# Schematic.net
KiCad netlist of a schematic drawn in EAGLE
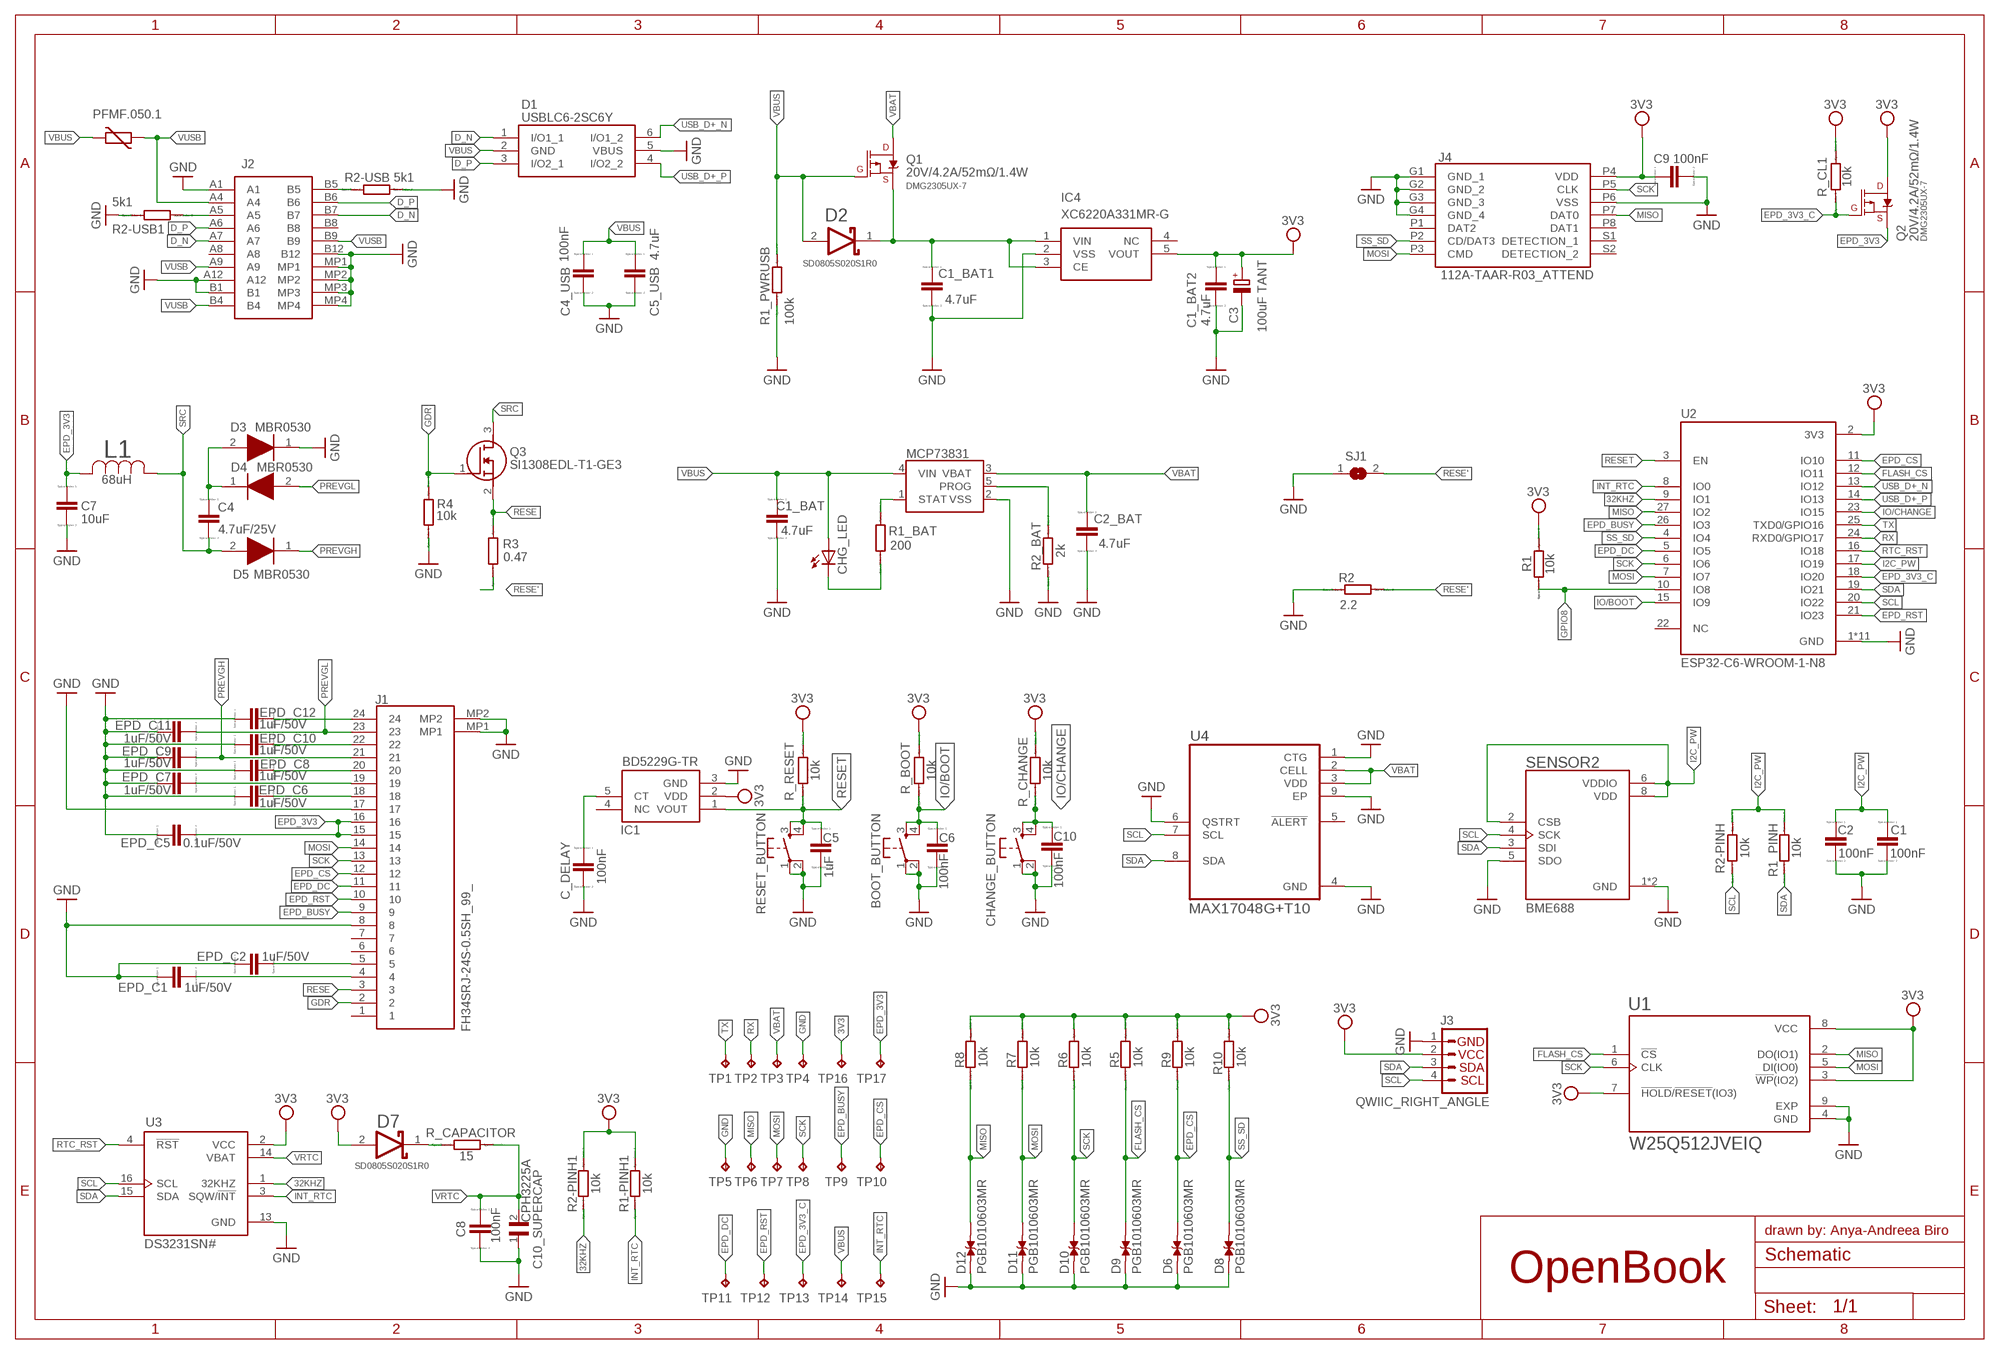
[diagram p0: schematic, sheet 1]

(export (version "E")
  (design (tool "Eeschema 10.0.6"))
  (components
    (comp (ref "BOOT_BUTTON")
      (value "BUTTON_CUSYOMV1")
      (footprint "eagle-import:MYBUTTON")
      (libsource (lib "eagle-import") (part "BUTTON_CUSYOMV1"))
    )
    (comp (ref "C1")
      (value "100nF")
      (footprint "eagle-import:ESP32_WROVER_EAGLE-LTSPICE_C0402")
      (libsource (lib "eagle-import") (part "ESP32_WROVER_EAGLE-LTSPICE_CC0402"))
    )
    (comp (ref "C1_BAT")
      (value "4.7uF")
      (footprint "eagle-import:ESP32_WROVER_EAGLE-LTSPICE_C0402")
      (libsource (lib "eagle-import") (part "ESP32_WROVER_EAGLE-LTSPICE_CC0402"))
    )
    (comp (ref "C1_BAT1")
      (value "4.7uF")
      (footprint "eagle-import:ESP32_WROVER_EAGLE-LTSPICE_C0402")
      (libsource (lib "eagle-import") (part "ESP32_WROVER_EAGLE-LTSPICE_CC0402"))
    )
    (comp (ref "C1_BAT2")
      (value "4.7uF")
      (footprint "eagle-import:ESP32_WROVER_EAGLE-LTSPICE_C0402")
      (libsource (lib "eagle-import") (part "ESP32_WROVER_EAGLE-LTSPICE_CC0402"))
    )
    (comp (ref "C2")
      (value "100nF")
      (footprint "eagle-import:ESP32_WROVER_EAGLE-LTSPICE_C0402")
      (libsource (lib "eagle-import") (part "ESP32_WROVER_EAGLE-LTSPICE_CC0402"))
    )
    (comp (ref "C2_BAT")
      (value "4.7uF")
      (footprint "eagle-import:ESP32_WROVER_EAGLE-LTSPICE_C0402")
      (libsource (lib "eagle-import") (part "ESP32_WROVER_EAGLE-LTSPICE_CC0402"))
    )
    (comp (ref "C3")
      (value "100uF TANT")
      (footprint "eagle-import:RCL_CT3528")
      (libsource (lib "eagle-import") (part "RCL_CPOL-EUCT3528"))
    )
    (comp (ref "C4")
      (value "4.7uF/25V")
      (footprint "eagle-import:ESP32_WROVER_EAGLE-LTSPICE_C0402")
      (libsource (lib "eagle-import") (part "ESP32_WROVER_EAGLE-LTSPICE_CC0402"))
    )
    (comp (ref "C4_USB")
      (value "100nF")
      (footprint "eagle-import:ESP32_WROVER_EAGLE-LTSPICE_C0402")
      (libsource (lib "eagle-import") (part "ESP32_WROVER_EAGLE-LTSPICE_CC0402"))
    )
    (comp (ref "C5")
      (value "1uF")
      (footprint "eagle-import:ESP32_WROVER_EAGLE-LTSPICE_C0402")
      (libsource (lib "eagle-import") (part "ESP32_WROVER_EAGLE-LTSPICE_CC0402"))
    )
    (comp (ref "C5_USB")
      (value "4.7uF")
      (footprint "eagle-import:ESP32_WROVER_EAGLE-LTSPICE_C0402")
      (libsource (lib "eagle-import") (part "ESP32_WROVER_EAGLE-LTSPICE_CC0402"))
    )
    (comp (ref "C6")
      (value "100nF")
      (footprint "eagle-import:ESP32_WROVER_EAGLE-LTSPICE_C0402")
      (libsource (lib "eagle-import") (part "ESP32_WROVER_EAGLE-LTSPICE_CC0402"))
    )
    (comp (ref "C7")
      (value "10uF")
      (footprint "eagle-import:ESP32_WROVER_EAGLE-LTSPICE_C0402")
      (libsource (lib "eagle-import") (part "ESP32_WROVER_EAGLE-LTSPICE_CC0402"))
    )
    (comp (ref "C8")
      (value "100nF")
      (footprint "eagle-import:ESP32_WROVER_EAGLE-LTSPICE_C0402")
      (libsource (lib "eagle-import") (part "ESP32_WROVER_EAGLE-LTSPICE_CC0402"))
    )
    (comp (ref "C9")
      (value "100nF")
      (footprint "eagle-import:ESP32_WROVER_EAGLE-LTSPICE_C0402")
      (libsource (lib "eagle-import") (part "ESP32_WROVER_EAGLE-LTSPICE_CC0402"))
    )
    (comp (ref "C10")
      (value "100nF")
      (footprint "eagle-import:ESP32_WROVER_EAGLE-LTSPICE_C0402")
      (libsource (lib "eagle-import") (part "ESP32_WROVER_EAGLE-LTSPICE_CC0402"))
    )
    (comp (ref "C10_SUPERCAP")
      (value "CPH3225A")
      (footprint "eagle-import:CAPCP3225X100N")
      (fields (field (name "MF") "Seiko Instruments"))
      (libsource (lib "eagle-import") (part "CPH3225A"))
    )
    (comp (ref "CHANGE_BUTTON")
      (value "BUTTON_CUSYOMV1")
      (footprint "eagle-import:MYBUTTON")
      (libsource (lib "eagle-import") (part "BUTTON_CUSYOMV1"))
    )
    (comp (ref "CHG_LED")
      (value "ADAFRUIT_LEDCHIP-LED0603")
      (footprint "eagle-import:ADAFRUIT_CHIP-LED0603")
      (libsource (lib "eagle-import") (part "ADAFRUIT_LEDCHIP-LED0603"))
    )
    (comp (ref "C_DELAY")
      (value "100nF")
      (footprint "eagle-import:ESP32_WROVER_EAGLE-LTSPICE_C0402")
      (libsource (lib "eagle-import") (part "ESP32_WROVER_EAGLE-LTSPICE_CC0402"))
    )
    (comp (ref "D1")
      (value "USBLC6-2SC6Y")
      (footprint "eagle-import:SOT95P280X145-6N")
      (fields (field (name "MF") "STMicroelectronics"))
      (libsource (lib "eagle-import") (part "USBLC6-2SC6Y"))
    )
    (comp (ref "D2")
      (value "ESP32_WROVER_AVX---SD0805S020S1R0_AVX_SD0805S020S1R0_0_0AVX_SD0805S020S1R0_0_0")
      (footprint "eagle-import:ESP32_WROVER_AVX---SD0805S020S1R0_AVX_SD0805S020S1R0_0")
      (fields
        (field (name "DIGIKEY_PART_NUMBER") "478-7800-1-ND")
        (field (name "MF") "AVX")
        (field (name "MOUSER_PART_NUMBER") "581-SD0805S020S1R0")
      )
      (libsource (lib "eagle-import") (part "ESP32_WROVER_AVX---SD0805S020S1R0_AVX_SD0805S020S1R0_0_0AVX_SD0805S020S1R0_0_0"))
    )
    (comp (ref "D3")
      (value "MBR0530")
      (footprint "eagle-import:SOD3716X135N")
      (fields (field (name "MF") "ON Semiconductor"))
      (libsource (lib "eagle-import") (part "MBR0530"))
    )
    (comp (ref "D4")
      (value "MBR0530")
      (footprint "eagle-import:SOD3716X135N")
      (fields (field (name "MF") "ON Semiconductor"))
      (libsource (lib "eagle-import") (part "MBR0530"))
    )
    (comp (ref "D5")
      (value "MBR0530")
      (footprint "eagle-import:SOD3716X135N")
      (fields (field (name "MF") "ON Semiconductor"))
      (libsource (lib "eagle-import") (part "MBR0530"))
    )
    (comp (ref "D6")
      (value "PGB1010603MR")
      (footprint "eagle-import:DIOC1608X36N")
      (fields (field (name "MF") "Littelfuse Inc."))
      (libsource (lib "eagle-import") (part "PGB1010603MR"))
    )
    (comp (ref "D7")
      (value "ESP32_WROVER_AVX---SD0805S020S1R0_AVX_SD0805S020S1R0_0_0AVX_SD0805S020S1R0_0_0")
      (footprint "eagle-import:ESP32_WROVER_AVX---SD0805S020S1R0_AVX_SD0805S020S1R0_0")
      (fields
        (field (name "DIGIKEY_PART_NUMBER") "478-7800-1-ND")
        (field (name "MF") "AVX")
        (field (name "MOUSER_PART_NUMBER") "581-SD0805S020S1R0")
      )
      (libsource (lib "eagle-import") (part "ESP32_WROVER_AVX---SD0805S020S1R0_AVX_SD0805S020S1R0_0_0AVX_SD0805S020S1R0_0_0"))
    )
    (comp (ref "D8")
      (value "PGB1010603MR")
      (footprint "eagle-import:DIOC1608X36N")
      (fields (field (name "MF") "Littelfuse Inc."))
      (libsource (lib "eagle-import") (part "PGB1010603MR"))
    )
    (comp (ref "D9")
      (value "PGB1010603MR")
      (footprint "eagle-import:DIOC1608X36N")
      (fields (field (name "MF") "Littelfuse Inc."))
      (libsource (lib "eagle-import") (part "PGB1010603MR"))
    )
    (comp (ref "D10")
      (value "PGB1010603MR")
      (footprint "eagle-import:DIOC1608X36N")
      (fields (field (name "MF") "Littelfuse Inc."))
      (libsource (lib "eagle-import") (part "PGB1010603MR"))
    )
    (comp (ref "D11")
      (value "PGB1010603MR")
      (footprint "eagle-import:DIOC1608X36N")
      (fields (field (name "MF") "Littelfuse Inc."))
      (libsource (lib "eagle-import") (part "PGB1010603MR"))
    )
    (comp (ref "D12")
      (value "PGB1010603MR")
      (footprint "eagle-import:DIOC1608X36N")
      (fields (field (name "MF") "Littelfuse Inc."))
      (libsource (lib "eagle-import") (part "PGB1010603MR"))
    )
    (comp (ref "EPD_C1")
      (value "1uF/50V")
      (footprint "eagle-import:ESP32_WROVER_EAGLE-LTSPICE_C0402")
      (libsource (lib "eagle-import") (part "ESP32_WROVER_EAGLE-LTSPICE_CC0402"))
    )
    (comp (ref "EPD_C2")
      (value "1uF/50V")
      (footprint "eagle-import:ESP32_WROVER_EAGLE-LTSPICE_C0402")
      (libsource (lib "eagle-import") (part "ESP32_WROVER_EAGLE-LTSPICE_CC0402"))
    )
    (comp (ref "EPD_C5")
      (value "0.1uF/50V")
      (footprint "eagle-import:ESP32_WROVER_EAGLE-LTSPICE_C0402")
      (libsource (lib "eagle-import") (part "ESP32_WROVER_EAGLE-LTSPICE_CC0402"))
    )
    (comp (ref "EPD_C6")
      (value "1uF/50V")
      (footprint "eagle-import:ESP32_WROVER_EAGLE-LTSPICE_C0402")
      (libsource (lib "eagle-import") (part "ESP32_WROVER_EAGLE-LTSPICE_CC0402"))
    )
    (comp (ref "EPD_C7")
      (value "1uF/50V")
      (footprint "eagle-import:ESP32_WROVER_EAGLE-LTSPICE_C0402")
      (libsource (lib "eagle-import") (part "ESP32_WROVER_EAGLE-LTSPICE_CC0402"))
    )
    (comp (ref "EPD_C8")
      (value "1uF/50V")
      (footprint "eagle-import:ESP32_WROVER_EAGLE-LTSPICE_C0402")
      (libsource (lib "eagle-import") (part "ESP32_WROVER_EAGLE-LTSPICE_CC0402"))
    )
    (comp (ref "EPD_C9")
      (value "1uF/50V")
      (footprint "eagle-import:ESP32_WROVER_EAGLE-LTSPICE_C0402")
      (libsource (lib "eagle-import") (part "ESP32_WROVER_EAGLE-LTSPICE_CC0402"))
    )
    (comp (ref "EPD_C10")
      (value "1uF/50V")
      (footprint "eagle-import:ESP32_WROVER_EAGLE-LTSPICE_C0402")
      (libsource (lib "eagle-import") (part "ESP32_WROVER_EAGLE-LTSPICE_CC0402"))
    )
    (comp (ref "EPD_C11")
      (value "1uF/50V")
      (footprint "eagle-import:ESP32_WROVER_EAGLE-LTSPICE_C0402")
      (libsource (lib "eagle-import") (part "ESP32_WROVER_EAGLE-LTSPICE_CC0402"))
    )
    (comp (ref "EPD_C12")
      (value "1uF/50V")
      (footprint "eagle-import:ESP32_WROVER_EAGLE-LTSPICE_C0402")
      (libsource (lib "eagle-import") (part "ESP32_WROVER_EAGLE-LTSPICE_CC0402"))
    )
    (comp (ref "IC1")
      (value "BD5229G-TR")
      (footprint "eagle-import:SOT95P280X125-5N")
      (fields (field (name "MOUSER_PART_NUMBER") "755-BD5229G-TR"))
      (libsource (lib "eagle-import") (part "BD5229G-TR"))
    )
    (comp (ref "IC4")
      (value "XC6220A331MR-G")
      (footprint "eagle-import:SOT95P280X120-5N")
      (fields (field (name "MOUSER_PART_NUMBER") "865-XC6220A331MR-G"))
      (libsource (lib "eagle-import") (part "XC6220A331MR-G"))
    )
    (comp (ref "J1")
      (value "FH34SRJ-24S-0.5SH_99_")
      (footprint "eagle-import:FH34SRJ24S05SH99")
      (fields
        (field (name "MANUFACTURER_PART_NUMBER") "FH34SRJ-24S-0.5SH(99)")
        (field (name "MOUSER_PART_NUMBER") "798-FH34SRJ24S05SH99")
      )
      (libsource (lib "eagle-import") (part "FH34SRJ-24S-0.5SH_99_"))
    )
    (comp (ref "J2")
      (value "SAMACSYS_PARTS_USB4110-GF-A")
      (footprint "eagle-import:SAMACSYS_PARTS_USB4110GFA")
      (fields
        (field (name "MANUFACTURER_PART_NUMBER") "USB4110-GF-A")
        (field (name "MOUSER_PART_NUMBER") "640-USB4110-GF-A")
      )
      (libsource (lib "eagle-import") (part "SAMACSYS_PARTS_USB4110-GF-A"))
    )
    (comp (ref "J3")
      (value "QWIIC_RIGHT_ANGLE")
      (footprint "eagle-import:JST04_1MM_RA")
      (libsource (lib "eagle-import") (part "QWIIC_CONNECTORJS-1MM"))
    )
    (comp (ref "J4")
      (value "112A-TAAR-R03_ATTEND")
      (footprint "eagle-import:112ATAARR03ATTEND")
      (fields (field (name "MANUFACTURER_PART_NUMBER") "112A-TAAR-R03 ATTEND"))
      (libsource (lib "eagle-import") (part "112A-TAAR-R03_ATTEND"))
    )
    (comp (ref "L1")
      (value "68uH")
      (footprint "eagle-import:IND_4828-WE-TPC_WRE")
      (fields
        (field (name "MANUFACTURER_PART_NUMBER") "744043680")
        (field (name "CUSTOM_VAL") "68uH")
        (field (name "COPYRIGHT") "Copyright (C) 2024 Ultra Librarian. All rights reserved.")
      )
      (libsource (lib "eagle-import") (part "744043680IND_4828-WE-TPC_WRE"))
    )
    (comp (ref "MCP73831")
      (value "ESP32_WROVER_SPARKFUN-IC-POWER_MCP73831")
      (footprint "eagle-import:ESP32_WROVER_SPARKFUN-IC-POWER_SOT23-5")
      (libsource (lib "eagle-import") (part "ESP32_WROVER_SPARKFUN-IC-POWER_MCP73831"))
    )
    (comp (ref "PFMF.050.1")
      (value "ESP32C6_VARISTORCN1812")
      (footprint "eagle-import:ESP32C6_VARISTOR_CT_CN1812")
      (libsource (lib "eagle-import") (part "ESP32C6_VARISTORCN1812"))
    )
    (comp (ref "Q1")
      (value "20V/4.2A/52mΩ/1.4W")
      (footprint "eagle-import:ESP32_WROVER_SPARKFUN-DISCRETESEMI_SOT23-3")
      (libsource (lib "eagle-import") (part "ESP32_WROVER_SPARKFUN-DISCRETESEMI_MOSFET_PCH-DMG2305UX-7"))
    )
    (comp (ref "Q2")
      (value "20V/4.2A/52mΩ/1.4W")
      (footprint "eagle-import:ESP32_WROVER_SPARKFUN-DISCRETESEMI_SOT23-3")
      (libsource (lib "eagle-import") (part "ESP32_WROVER_SPARKFUN-DISCRETESEMI_MOSFET_PCH-DMG2305UX-7"))
    )
    (comp (ref "Q3")
      (value "SI1308EDL-T1-GE3")
      (footprint "eagle-import:SOT65P210X110-3N")
      (fields (field (name "MF") "Vishay Siliconix"))
      (libsource (lib "eagle-import") (part "SI1308EDL-T1-GE3"))
    )
    (comp (ref "R1")
      (value "10k")
      (footprint "eagle-import:ESP32_WROVER_EAGLE-LTSPICE_R0402")
      (libsource (lib "eagle-import") (part "ESP32_WROVER_EAGLE-LTSPICE_RR0402"))
    )
    (comp (ref "R1-PINH1")
      (value "10k")
      (footprint "eagle-import:ESP32_WROVER_EAGLE-LTSPICE_R0402")
      (libsource (lib "eagle-import") (part "ESP32_WROVER_EAGLE-LTSPICE_RR0402"))
    )
    (comp (ref "R1_BAT")
      (value "200")
      (footprint "eagle-import:ESP32_WROVER_EAGLE-LTSPICE_R0402")
      (libsource (lib "eagle-import") (part "ESP32_WROVER_EAGLE-LTSPICE_RR0402"))
    )
    (comp (ref "R1_PINH")
      (value "10k")
      (footprint "eagle-import:ESP32_WROVER_EAGLE-LTSPICE_R0402")
      (libsource (lib "eagle-import") (part "ESP32_WROVER_EAGLE-LTSPICE_RR0402"))
    )
    (comp (ref "R1_PWRUSB")
      (value "100k")
      (footprint "eagle-import:ESP32_WROVER_EAGLE-LTSPICE_R0402")
      (libsource (lib "eagle-import") (part "ESP32_WROVER_EAGLE-LTSPICE_RR0402"))
    )
    (comp (ref "R2")
      (value "2.2")
      (footprint "eagle-import:ESP32_WROVER_EAGLE-LTSPICE_R0402")
      (libsource (lib "eagle-import") (part "ESP32_WROVER_EAGLE-LTSPICE_RR0402"))
    )
    (comp (ref "R2-PINH")
      (value "10k")
      (footprint "eagle-import:ESP32_WROVER_EAGLE-LTSPICE_R0402")
      (libsource (lib "eagle-import") (part "ESP32_WROVER_EAGLE-LTSPICE_RR0402"))
    )
    (comp (ref "R2-PINH1")
      (value "10k")
      (footprint "eagle-import:ESP32_WROVER_EAGLE-LTSPICE_R0402")
      (libsource (lib "eagle-import") (part "ESP32_WROVER_EAGLE-LTSPICE_RR0402"))
    )
    (comp (ref "R2-USB")
      (value "5k1")
      (footprint "eagle-import:ESP32_WROVER_EAGLE-LTSPICE_R0402")
      (libsource (lib "eagle-import") (part "ESP32_WROVER_EAGLE-LTSPICE_RR0402"))
    )
    (comp (ref "R2-USB1")
      (value "5k1")
      (footprint "eagle-import:ESP32_WROVER_EAGLE-LTSPICE_R0402")
      (libsource (lib "eagle-import") (part "ESP32_WROVER_EAGLE-LTSPICE_RR0402"))
    )
    (comp (ref "R2_BAT")
      (value "2k")
      (footprint "eagle-import:ESP32_WROVER_EAGLE-LTSPICE_R0402")
      (libsource (lib "eagle-import") (part "ESP32_WROVER_EAGLE-LTSPICE_RR0402"))
    )
    (comp (ref "R3")
      (value "0.47")
      (footprint "eagle-import:ESP32_WROVER_EAGLE-LTSPICE_R0402")
      (libsource (lib "eagle-import") (part "ESP32_WROVER_EAGLE-LTSPICE_RR0402"))
    )
    (comp (ref "R4")
      (value "10k")
      (footprint "eagle-import:ESP32_WROVER_EAGLE-LTSPICE_R0402")
      (libsource (lib "eagle-import") (part "ESP32_WROVER_EAGLE-LTSPICE_RR0402"))
    )
    (comp (ref "R5")
      (value "10k")
      (footprint "eagle-import:ESP32_WROVER_EAGLE-LTSPICE_R0402")
      (libsource (lib "eagle-import") (part "ESP32_WROVER_EAGLE-LTSPICE_RR0402"))
    )
    (comp (ref "R6")
      (value "10k")
      (footprint "eagle-import:ESP32_WROVER_EAGLE-LTSPICE_R0402")
      (libsource (lib "eagle-import") (part "ESP32_WROVER_EAGLE-LTSPICE_RR0402"))
    )
    (comp (ref "R7")
      (value "10k")
      (footprint "eagle-import:ESP32_WROVER_EAGLE-LTSPICE_R0402")
      (libsource (lib "eagle-import") (part "ESP32_WROVER_EAGLE-LTSPICE_RR0402"))
    )
    (comp (ref "R8")
      (value "10k")
      (footprint "eagle-import:ESP32_WROVER_EAGLE-LTSPICE_R0402")
      (libsource (lib "eagle-import") (part "ESP32_WROVER_EAGLE-LTSPICE_RR0402"))
    )
    (comp (ref "R9")
      (value "10k")
      (footprint "eagle-import:ESP32_WROVER_EAGLE-LTSPICE_R0402")
      (libsource (lib "eagle-import") (part "ESP32_WROVER_EAGLE-LTSPICE_RR0402"))
    )
    (comp (ref "R10")
      (value "10k")
      (footprint "eagle-import:ESP32_WROVER_EAGLE-LTSPICE_R0402")
      (libsource (lib "eagle-import") (part "ESP32_WROVER_EAGLE-LTSPICE_RR0402"))
    )
    (comp (ref "RESET_BUTTON")
      (value "BUTTON_CUSYOMV1")
      (footprint "eagle-import:MYBUTTON")
      (libsource (lib "eagle-import") (part "BUTTON_CUSYOMV1"))
    )
    (comp (ref "R_BOOT")
      (value "10k")
      (footprint "eagle-import:ESP32_WROVER_EAGLE-LTSPICE_R0402")
      (libsource (lib "eagle-import") (part "ESP32_WROVER_EAGLE-LTSPICE_RR0402"))
    )
    (comp (ref "R_CAPACITOR")
      (value "15")
      (footprint "eagle-import:ESP32_WROVER_EAGLE-LTSPICE_R0402")
      (libsource (lib "eagle-import") (part "ESP32_WROVER_EAGLE-LTSPICE_RR0402"))
    )
    (comp (ref "R_CHANGE")
      (value "10k")
      (footprint "eagle-import:ESP32_WROVER_EAGLE-LTSPICE_R0402")
      (libsource (lib "eagle-import") (part "ESP32_WROVER_EAGLE-LTSPICE_RR0402"))
    )
    (comp (ref "R_CL1")
      (value "10k")
      (footprint "eagle-import:ESP32_WROVER_EAGLE-LTSPICE_R0402")
      (libsource (lib "eagle-import") (part "ESP32_WROVER_EAGLE-LTSPICE_RR0402"))
    )
    (comp (ref "R_RESET")
      (value "10k")
      (footprint "eagle-import:ESP32_WROVER_EAGLE-LTSPICE_R0402")
      (libsource (lib "eagle-import") (part "ESP32_WROVER_EAGLE-LTSPICE_RR0402"))
    )
    (comp (ref "SENSOR2")
      (value "ESP32_WROVER_BME680_BME680")
      (footprint "eagle-import:ESP32_WROVER_BME680_PSON80P300X300X100-8N")
      (fields (field (name "MF") "Bosch Sensortec") (field (name "MP") "BME680"))
      (libsource (lib "eagle-import") (part "ESP32_WROVER_BME680_BME680"))
    )
    (comp (ref "SJ1") (value "SJ") (footprint "eagle-import:SJ") (libsource (lib "eagle-import") (part "SJ")))
    (comp (ref "TP1")
      (value "TPTP20R")
      (footprint "eagle-import:TP20R")
      (libsource (lib "eagle-import") (part "TPTP20R"))
    )
    (comp (ref "TP2")
      (value "TPTP20R")
      (footprint "eagle-import:TP20R")
      (libsource (lib "eagle-import") (part "TPTP20R"))
    )
    (comp (ref "TP3")
      (value "TPTP20R")
      (footprint "eagle-import:TP20R")
      (libsource (lib "eagle-import") (part "TPTP20R"))
    )
    (comp (ref "TP4")
      (value "TPTP20R")
      (footprint "eagle-import:TP20R")
      (libsource (lib "eagle-import") (part "TPTP20R"))
    )
    (comp (ref "TP5")
      (value "TPTP20R")
      (footprint "eagle-import:TP20R")
      (libsource (lib "eagle-import") (part "TPTP20R"))
    )
    (comp (ref "TP6")
      (value "TPTP20R")
      (footprint "eagle-import:TP20R")
      (libsource (lib "eagle-import") (part "TPTP20R"))
    )
    (comp (ref "TP7")
      (value "TPTP20R")
      (footprint "eagle-import:TP20R")
      (libsource (lib "eagle-import") (part "TPTP20R"))
    )
    (comp (ref "TP8")
      (value "TPTP20R")
      (footprint "eagle-import:TP20R")
      (libsource (lib "eagle-import") (part "TPTP20R"))
    )
    (comp (ref "TP9")
      (value "TPTP20R")
      (footprint "eagle-import:TP20R")
      (libsource (lib "eagle-import") (part "TPTP20R"))
    )
    (comp (ref "TP10")
      (value "TPTP20R")
      (footprint "eagle-import:TP20R")
      (libsource (lib "eagle-import") (part "TPTP20R"))
    )
    (comp (ref "TP11")
      (value "TPTP20R")
      (footprint "eagle-import:TP20R")
      (libsource (lib "eagle-import") (part "TPTP20R"))
    )
    (comp (ref "TP12")
      (value "TPTP20R")
      (footprint "eagle-import:TP20R")
      (libsource (lib "eagle-import") (part "TPTP20R"))
    )
    (comp (ref "TP13")
      (value "TPTP20R")
      (footprint "eagle-import:TP20R")
      (libsource (lib "eagle-import") (part "TPTP20R"))
    )
    (comp (ref "TP14")
      (value "TPTP20R")
      (footprint "eagle-import:TP20R")
      (libsource (lib "eagle-import") (part "TPTP20R"))
    )
    (comp (ref "TP15")
      (value "TPTP20R")
      (footprint "eagle-import:TP20R")
      (libsource (lib "eagle-import") (part "TPTP20R"))
    )
    (comp (ref "TP16")
      (value "TPTP20R")
      (footprint "eagle-import:TP20R")
      (libsource (lib "eagle-import") (part "TPTP20R"))
    )
    (comp (ref "TP17")
      (value "TPTP20R")
      (footprint "eagle-import:TP20R")
      (libsource (lib "eagle-import") (part "TPTP20R"))
    )
    (comp (ref "U1")
      (value "W25Q512JVEIQ")
      (footprint "eagle-import:SON127P600X800X80-9N")
      (fields (field (name "MF") "Winbond Electronics"))
      (libsource (lib "eagle-import") (part "W25Q512JVEIQ"))
    )
    (comp (ref "U2")
      (value "ESP32-C6-WROOM-1-N8")
      (footprint "eagle-import:XCVR_ESP32-C6-WROOM-1-N8")
      (fields (field (name "MF") "Espressif Systems"))
      (libsource (lib "eagle-import") (part "ESP32-C6-WROOM-1-N8"))
    )
    (comp (ref "U3")
      (value "DS3231SN#")
      (footprint "eagle-import:SOIC127P1032X265-16N")
      (fields (field (name "MF") "Analog Devices"))
      (libsource (lib "eagle-import") (part "DS3231SN#"))
    )
    (comp (ref "U4")
      (value "MAX17048G+T10")
      (footprint "eagle-import:SON50P200X200X80-9N")
      (fields (field (name "MF") "Analog Devices"))
      (libsource (lib "eagle-import") (part "MAX17048G+T10"))
    )
  )
  (nets
    (net (code "1") (name "3V3") (class "Default")
      (node (ref "C1_BAT2") (pin "1") (pinfunction "1_1") (pintype "passive"))
      (node (ref "C3") (pin "+") (pinfunction "+_+") (pintype "passive"))
      (node (ref "C9") (pin "1") (pinfunction "1_1") (pintype "passive"))
      (node (ref "D7") (pin "2") (pinfunction "ANODE_2") (pintype "bidirectional"))
      (node (ref "IC1") (pin "2") (pinfunction "VDD_2") (pintype "bidirectional"))
      (node (ref "IC4") (pin "5") (pinfunction "VOUT_5") (pintype "bidirectional"))
      (node (ref "J3") (pin "2") (pinfunction "2_2") (pintype "power_in"))
      (node (ref "J4") (pin "P4") (pinfunction "VDD_P4") (pintype "bidirectional"))
      (node (ref "Q2") (pin "3") (pinfunction "D_3") (pintype "bidirectional"))
      (node (ref "R1") (pin "2") (pinfunction "2_2") (pintype "passive"))
      (node (ref "R1-PINH1") (pin "2") (pinfunction "2_2") (pintype "passive"))
      (node (ref "R10") (pin "2") (pinfunction "2_2") (pintype "passive"))
      (node (ref "R2-PINH1") (pin "2") (pinfunction "2_2") (pintype "passive"))
      (node (ref "R5") (pin "2") (pinfunction "2_2") (pintype "passive"))
      (node (ref "R6") (pin "2") (pinfunction "2_2") (pintype "passive"))
      (node (ref "R7") (pin "2") (pinfunction "2_2") (pintype "passive"))
      (node (ref "R8") (pin "2") (pinfunction "2_2") (pintype "passive"))
      (node (ref "R9") (pin "2") (pinfunction "2_2") (pintype "passive"))
      (node (ref "R_BOOT") (pin "2") (pinfunction "2_2") (pintype "passive"))
      (node (ref "R_CHANGE") (pin "2") (pinfunction "2_2") (pintype "passive"))
      (node (ref "R_CL1") (pin "2") (pinfunction "2_2") (pintype "passive"))
      (node (ref "R_RESET") (pin "2") (pinfunction "2_2") (pintype "passive"))
      (node (ref "TP16") (pin "TP") (pinfunction "TP_TP") (pintype "input"))
      (node (ref "U1") (pin "3") (pinfunction "~{WP}(IO2)_3") (pintype "bidirectional"))
      (node (ref "U1") (pin "7") (pinfunction "~{HOLD}/~{RESET}(IO3)_7") (pintype "bidirectional"))
      (node (ref "U1") (pin "8") (pinfunction "VCC_8") (pintype "power_in"))
      (node (ref "U2") (pin "2") (pinfunction "3V3_2") (pintype "power_in"))
      (node (ref "U3") (pin "2") (pinfunction "VCC_2") (pintype "power_in"))
    )
    (net (code "2") (name "32KHZ") (class "Default")
      (node (ref "R2-PINH1") (pin "1") (pinfunction "1_1") (pintype "passive"))
      (node (ref "U2") (pin "9") (pinfunction "IO1_9") (pintype "bidirectional"))
      (node (ref "U3") (pin "1") (pinfunction "32KHZ_1") (pintype "output"))
    )
    (net (code "3") (name "D_N") (class "Default")
      (node (ref "D1") (pin "1") (pinfunction "I/O1_1_1") (pintype "bidirectional"))
      (node (ref "J2") (pin "A7") (pinfunction "A7_A7") (pintype "bidirectional"))
      (node (ref "J2") (pin "B7") (pinfunction "B7_B7") (pintype "bidirectional"))
    )
    (net (code "4") (name "D_P") (class "Default")
      (node (ref "D1") (pin "3") (pinfunction "I/O2_1_3") (pintype "bidirectional"))
      (node (ref "J2") (pin "A6") (pinfunction "A6_A6") (pintype "bidirectional"))
      (node (ref "J2") (pin "B6") (pinfunction "B6_B6") (pintype "bidirectional"))
    )
    (net (code "5") (name "EPD_3V3") (class "Default")
      (node (ref "C7") (pin "1") (pinfunction "1_1") (pintype "passive"))
      (node (ref "EPD_C5") (pin "2") (pinfunction "2_2") (pintype "passive"))
      (node (ref "J1") (pin "15") (pinfunction "15_15") (pintype "bidirectional"))
      (node (ref "J1") (pin "16") (pinfunction "16_16") (pintype "bidirectional"))
      (node (ref "L1") (pin "2") (pinfunction "2_2") (pintype "passive"))
      (node (ref "Q2") (pin "2") (pinfunction "S_2") (pintype "bidirectional"))
      (node (ref "TP17") (pin "TP") (pinfunction "TP_TP") (pintype "input"))
    )
    (net (code "6") (name "EPD_3V3_C") (class "Default")
      (node (ref "Q2") (pin "1") (pinfunction "G_1") (pintype "bidirectional"))
      (node (ref "R_CL1") (pin "1") (pinfunction "1_1") (pintype "passive"))
      (node (ref "TP13") (pin "TP") (pinfunction "TP_TP") (pintype "input"))
      (node (ref "U2") (pin "18") (pinfunction "IO20_18") (pintype "bidirectional"))
    )
    (net (code "7") (name "EPD_BUSY") (class "Default")
      (node (ref "J1") (pin "9") (pinfunction "9_9") (pintype "bidirectional"))
      (node (ref "TP9") (pin "TP") (pinfunction "TP_TP") (pintype "input"))
      (node (ref "U2") (pin "26") (pinfunction "IO3_26") (pintype "bidirectional"))
    )
    (net (code "8") (name "EPD_CS") (class "Default")
      (node (ref "D6") (pin "2") (pinfunction "2_2") (pintype "passive"))
      (node (ref "J1") (pin "12") (pinfunction "12_12") (pintype "bidirectional"))
      (node (ref "R9") (pin "1") (pinfunction "1_1") (pintype "passive"))
      (node (ref "TP10") (pin "TP") (pinfunction "TP_TP") (pintype "input"))
      (node (ref "U2") (pin "11") (pinfunction "IO10_11") (pintype "bidirectional"))
    )
    (net (code "9") (name "EPD_DC") (class "Default")
      (node (ref "J1") (pin "11") (pinfunction "11_11") (pintype "bidirectional"))
      (node (ref "TP11") (pin "TP") (pinfunction "TP_TP") (pintype "input"))
      (node (ref "U2") (pin "5") (pinfunction "IO5_5") (pintype "bidirectional"))
    )
    (net (code "10") (name "EPD_RST") (class "Default")
      (node (ref "J1") (pin "10") (pinfunction "10_10") (pintype "bidirectional"))
      (node (ref "TP12") (pin "TP") (pinfunction "TP_TP") (pintype "input"))
      (node (ref "U2") (pin "21") (pinfunction "IO23_21") (pintype "bidirectional"))
    )
    (net (code "11") (name "FLASH_CS") (class "Default")
      (node (ref "D9") (pin "2") (pinfunction "2_2") (pintype "passive"))
      (node (ref "R5") (pin "1") (pinfunction "1_1") (pintype "passive"))
      (node (ref "U1") (pin "1") (pinfunction "~{CS}_1") (pintype "input"))
      (node (ref "U2") (pin "12") (pinfunction "IO11_12") (pintype "bidirectional"))
    )
    (net (code "12") (name "GDR") (class "Default")
      (node (ref "J1") (pin "2") (pinfunction "2_2") (pintype "bidirectional"))
      (node (ref "Q3") (pin "1") (pinfunction "G_1") (pintype "bidirectional"))
      (node (ref "R4") (pin "2") (pinfunction "2_2") (pintype "passive"))
    )
    (net (code "13") (name "GND") (class "Default")
      (node (ref "BOOT_BUTTON") (pin "1") (pinfunction "1_1") (pintype "passive"))
      (node (ref "BOOT_BUTTON") (pin "2") (pinfunction "2_2") (pintype "passive"))
      (node (ref "C1") (pin "2") (pinfunction "2_2") (pintype "passive"))
      (node (ref "C10") (pin "2") (pinfunction "2_2") (pintype "passive"))
      (node (ref "C10_SUPERCAP") (pin "1") (pinfunction "1_1") (pintype "passive"))
      (node (ref "C1_BAT") (pin "2") (pinfunction "2_2") (pintype "passive"))
      (node (ref "C1_BAT1") (pin "2") (pinfunction "2_2") (pintype "passive"))
      (node (ref "C1_BAT2") (pin "2") (pinfunction "2_2") (pintype "passive"))
      (node (ref "C2") (pin "2") (pinfunction "2_2") (pintype "passive"))
      (node (ref "C2_BAT") (pin "2") (pinfunction "2_2") (pintype "passive"))
      (node (ref "C3") (pin "-") (pinfunction "-_-") (pintype "passive"))
      (node (ref "C4_USB") (pin "2") (pinfunction "2_2") (pintype "passive"))
      (node (ref "C5") (pin "2") (pinfunction "2_2") (pintype "passive"))
      (node (ref "C5_USB") (pin "2") (pinfunction "2_2") (pintype "passive"))
      (node (ref "C6") (pin "2") (pinfunction "2_2") (pintype "passive"))
      (node (ref "C7") (pin "2") (pinfunction "2_2") (pintype "passive"))
      (node (ref "C8") (pin "2") (pinfunction "2_2") (pintype "passive"))
      (node (ref "C9") (pin "2") (pinfunction "2_2") (pintype "passive"))
      (node (ref "CHANGE_BUTTON") (pin "1") (pinfunction "1_1") (pintype "passive"))
      (node (ref "CHANGE_BUTTON") (pin "2") (pinfunction "2_2") (pintype "passive"))
      (node (ref "C_DELAY") (pin "2") (pinfunction "2_2") (pintype "passive"))
      (node (ref "D1") (pin "5") (pinfunction "VBUS_5") (pintype "bidirectional"))
      (node (ref "D10") (pin "1") (pinfunction "1_1") (pintype "passive"))
      (node (ref "D11") (pin "1") (pinfunction "1_1") (pintype "passive"))
      (node (ref "D12") (pin "1") (pinfunction "1_1") (pintype "passive"))
      (node (ref "D3") (pin "1") (pinfunction "K_1") (pintype "bidirectional"))
      (node (ref "D6") (pin "1") (pinfunction "1_1") (pintype "passive"))
      (node (ref "D8") (pin "1") (pinfunction "1_1") (pintype "passive"))
      (node (ref "D9") (pin "1") (pinfunction "1_1") (pintype "passive"))
      (node (ref "EPD_C1") (pin "1") (pinfunction "1_1") (pintype "passive"))
      (node (ref "EPD_C10") (pin "1") (pinfunction "1_1") (pintype "passive"))
      (node (ref "EPD_C11") (pin "1") (pinfunction "1_1") (pintype "passive"))
      (node (ref "EPD_C12") (pin "1") (pinfunction "1_1") (pintype "passive"))
      (node (ref "EPD_C2") (pin "1") (pinfunction "1_1") (pintype "passive"))
      (node (ref "EPD_C5") (pin "1") (pinfunction "1_1") (pintype "passive"))
      (node (ref "EPD_C6") (pin "1") (pinfunction "1_1") (pintype "passive"))
      (node (ref "EPD_C7") (pin "1") (pinfunction "1_1") (pintype "passive"))
      (node (ref "EPD_C8") (pin "1") (pinfunction "1_1") (pintype "passive"))
      (node (ref "EPD_C9") (pin "1") (pinfunction "1_1") (pintype "passive"))
      (node (ref "IC1") (pin "3") (pinfunction "GND_3") (pintype "bidirectional"))
      (node (ref "IC4") (pin "2") (pinfunction "VSS_2") (pintype "bidirectional"))
      (node (ref "J1") (pin "17") (pinfunction "17_17") (pintype "bidirectional"))
      (node (ref "J1") (pin "8") (pinfunction "8_8") (pintype "bidirectional"))
      (node (ref "J1") (pin "MP1") (pinfunction "MP1_MP1") (pintype "bidirectional"))
      (node (ref "J1") (pin "MP2") (pinfunction "MP2_MP2") (pintype "bidirectional"))
      (node (ref "J2") (pin "A1") (pinfunction "A1_A1") (pintype "bidirectional"))
      (node (ref "J2") (pin "A12") (pinfunction "A12_A12") (pintype "bidirectional"))
      (node (ref "J2") (pin "B1") (pinfunction "B1_B1") (pintype "bidirectional"))
      (node (ref "J2") (pin "B12") (pinfunction "B12_B12") (pintype "bidirectional"))
      (node (ref "J2") (pin "MP1") (pinfunction "MP1_MP1") (pintype "bidirectional"))
      (node (ref "J2") (pin "MP2") (pinfunction "MP2_MP2") (pintype "bidirectional"))
      (node (ref "J2") (pin "MP3") (pinfunction "MP3_MP3") (pintype "bidirectional"))
      (node (ref "J2") (pin "MP4") (pinfunction "MP4_MP4") (pintype "bidirectional"))
      (node (ref "J3") (pin "1") (pinfunction "1_1") (pintype "power_in"))
      (node (ref "J4") (pin "G1") (pinfunction "GND_1_G1") (pintype "bidirectional"))
      (node (ref "J4") (pin "G2") (pinfunction "GND_2_G2") (pintype "bidirectional"))
      (node (ref "J4") (pin "G3") (pinfunction "GND_3_G3") (pintype "bidirectional"))
      (node (ref "J4") (pin "G4") (pinfunction "GND_4_G4") (pintype "bidirectional"))
      (node (ref "J4") (pin "P6") (pinfunction "VSS_P6") (pintype "bidirectional"))
      (node (ref "MCP73831") (pin "2") (pinfunction "VSS_2") (pintype "power_in"))
      (node (ref "R1_PWRUSB") (pin "1") (pinfunction "1_1") (pintype "passive"))
      (node (ref "R2") (pin "1") (pinfunction "1_1") (pintype "passive"))
      (node (ref "R2-USB") (pin "2") (pinfunction "2_2") (pintype "passive"))
      (node (ref "R2-USB1") (pin "1") (pinfunction "1_1") (pintype "passive"))
      (node (ref "R2_BAT") (pin "1") (pinfunction "1_1") (pintype "passive"))
      (node (ref "R4") (pin "1") (pinfunction "1_1") (pintype "passive"))
      (node (ref "RESET_BUTTON") (pin "1") (pinfunction "1_1") (pintype "passive"))
      (node (ref "RESET_BUTTON") (pin "2") (pinfunction "2_2") (pintype "passive"))
      (node (ref "SENSOR2") (pin "1") (pinfunction "GND_1") (pintype "power_in"))
      (node (ref "SENSOR2") (pin "5") (pinfunction "SDO_5") (pintype "bidirectional"))
      (node (ref "SENSOR2") (pin "7") (pinfunction "GND_7") (pintype "power_in"))
      (node (ref "SJ1") (pin "1") (pinfunction "1_1") (pintype "passive"))
      (node (ref "TP4") (pin "TP") (pinfunction "TP_TP") (pintype "input"))
      (node (ref "TP5") (pin "TP") (pinfunction "TP_TP") (pintype "input"))
      (node (ref "U1") (pin "4") (pinfunction "GND_4") (pintype "power_in"))
      (node (ref "U1") (pin "9") (pinfunction "EXP_9") (pintype "passive"))
      (node (ref "U2") (pin "1") (pinfunction "GND_1") (pintype "power_in"))
      (node (ref "U2") (pin "28") (pinfunction "GND_28") (pintype "power_in"))
      (node (ref "U2") (pin "29_1") (pinfunction "GND_29_1") (pintype "power_in"))
      (node (ref "U2") (pin "29_2") (pinfunction "GND_29_2") (pintype "power_in"))
      (node (ref "U2") (pin "29_3") (pinfunction "GND_29_3") (pintype "power_in"))
      (node (ref "U2") (pin "29_4") (pinfunction "GND_29_4") (pintype "power_in"))
      (node (ref "U2") (pin "29_5") (pinfunction "GND_29_5") (pintype "power_in"))
      (node (ref "U2") (pin "29_6") (pinfunction "GND_29_6") (pintype "power_in"))
      (node (ref "U2") (pin "29_7") (pinfunction "GND_29_7") (pintype "power_in"))
      (node (ref "U2") (pin "29_8") (pinfunction "GND_29_8") (pintype "power_in"))
      (node (ref "U2") (pin "29_9") (pinfunction "GND_29_9") (pintype "power_in"))
      (node (ref "U3") (pin "13") (pinfunction "GND_13") (pintype "power_in"))
      (node (ref "U4") (pin "1") (pinfunction "CTG_1") (pintype "power_in"))
      (node (ref "U4") (pin "4") (pinfunction "GND_4") (pintype "power_in"))
      (node (ref "U4") (pin "6") (pinfunction "QSTRT_6") (pintype "input"))
      (node (ref "U4") (pin "9") (pinfunction "EP_9") (pintype "power_in"))
    )
    (net (code "14") (name "GPIO8") (class "Default")
      (node (ref "R1") (pin "1") (pinfunction "1_1") (pintype "passive"))
      (node (ref "U2") (pin "10") (pinfunction "IO8_10") (pintype "bidirectional"))
    )
    (net (code "15") (name "I2C_PW") (class "Default")
      (node (ref "C1") (pin "1") (pinfunction "1_1") (pintype "passive"))
      (node (ref "C2") (pin "1") (pinfunction "1_1") (pintype "passive"))
      (node (ref "R1_PINH") (pin "2") (pinfunction "2_2") (pintype "passive"))
      (node (ref "R2-PINH") (pin "2") (pinfunction "2_2") (pintype "passive"))
      (node (ref "SENSOR2") (pin "2") (pinfunction "CSB_2") (pintype "input"))
      (node (ref "SENSOR2") (pin "6") (pinfunction "VDDIO_6") (pintype "power_in"))
      (node (ref "SENSOR2") (pin "8") (pinfunction "VDD_8") (pintype "power_in"))
      (node (ref "U2") (pin "17") (pinfunction "IO19_17") (pintype "bidirectional"))
    )
    (net (code "16") (name "INT_RTC") (class "Default")
      (node (ref "R1-PINH1") (pin "1") (pinfunction "1_1") (pintype "passive"))
      (node (ref "TP15") (pin "TP") (pinfunction "TP_TP") (pintype "input"))
      (node (ref "U2") (pin "8") (pinfunction "IO0_8") (pintype "bidirectional"))
      (node (ref "U3") (pin "3") (pinfunction "SQW/~{INT}_3") (pintype "output"))
    )
    (net (code "17") (name "IO{slash}BOOT") (class "Default")
      (node (ref "BOOT_BUTTON") (pin "3") (pinfunction "3_3") (pintype "passive"))
      (node (ref "BOOT_BUTTON") (pin "4") (pinfunction "4_4") (pintype "passive"))
      (node (ref "C6") (pin "1") (pinfunction "1_1") (pintype "passive"))
      (node (ref "R_BOOT") (pin "1") (pinfunction "1_1") (pintype "passive"))
      (node (ref "U2") (pin "15") (pinfunction "IO9_15") (pintype "bidirectional"))
    )
    (net (code "18") (name "IO{slash}CHANGE") (class "Default")
      (node (ref "C10") (pin "1") (pinfunction "1_1") (pintype "passive"))
      (node (ref "CHANGE_BUTTON") (pin "3") (pinfunction "3_3") (pintype "passive"))
      (node (ref "CHANGE_BUTTON") (pin "4") (pinfunction "4_4") (pintype "passive"))
      (node (ref "R_CHANGE") (pin "1") (pinfunction "1_1") (pintype "passive"))
      (node (ref "U2") (pin "23") (pinfunction "IO15_23") (pintype "bidirectional"))
    )
    (net (code "19") (name "MISO") (class "Default")
      (node (ref "D12") (pin "2") (pinfunction "2_2") (pintype "passive"))
      (node (ref "J4") (pin "P7") (pinfunction "DAT0_P7") (pintype "bidirectional"))
      (node (ref "R8") (pin "1") (pinfunction "1_1") (pintype "passive"))
      (node (ref "TP6") (pin "TP") (pinfunction "TP_TP") (pintype "input"))
      (node (ref "U1") (pin "2") (pinfunction "DO(IO1)_2") (pintype "bidirectional"))
      (node (ref "U2") (pin "27") (pinfunction "IO2_27") (pintype "bidirectional"))
    )
    (net (code "20") (name "MOSI") (class "Default")
      (node (ref "D11") (pin "2") (pinfunction "2_2") (pintype "passive"))
      (node (ref "J1") (pin "14") (pinfunction "14_14") (pintype "bidirectional"))
      (node (ref "J4") (pin "P3") (pinfunction "CMD_P3") (pintype "bidirectional"))
      (node (ref "R7") (pin "1") (pinfunction "1_1") (pintype "passive"))
      (node (ref "TP7") (pin "TP") (pinfunction "TP_TP") (pintype "input"))
      (node (ref "U1") (pin "5") (pinfunction "DI(IO0)_5") (pintype "bidirectional"))
      (node (ref "U2") (pin "7") (pinfunction "IO7_7") (pintype "bidirectional"))
    )
    (net (code "21") (name "Net-(CHG_LED-PadC)") (class "Default")
      (node (ref "CHG_LED") (pin "C") (pinfunction "C_C") (pintype "passive"))
      (node (ref "R1_BAT") (pin "1") (pinfunction "1_1") (pintype "passive"))
    )
    (net (code "22") (name "Net-(D2-CATHODE)") (class "Default")
      (node (ref "C1_BAT1") (pin "1") (pinfunction "1_1") (pintype "passive"))
      (node (ref "D2") (pin "1") (pinfunction "CATHODE_1") (pintype "bidirectional"))
      (node (ref "IC4") (pin "1") (pinfunction "VIN_1") (pintype "bidirectional"))
      (node (ref "IC4") (pin "3") (pinfunction "CE_3") (pintype "bidirectional"))
      (node (ref "Q1") (pin "2") (pinfunction "S_2") (pintype "bidirectional"))
    )
    (net (code "23") (name "Net-(D3-A)") (class "Default")
      (node (ref "C4") (pin "1") (pinfunction "1_1") (pintype "passive"))
      (node (ref "D3") (pin "2") (pinfunction "A_2") (pintype "bidirectional"))
      (node (ref "D4") (pin "1") (pinfunction "K_1") (pintype "bidirectional"))
    )
    (net (code "24") (name "Net-(D7-CATHODE)") (class "Default")
      (node (ref "D7") (pin "1") (pinfunction "CATHODE_1") (pintype "bidirectional"))
      (node (ref "R_CAPACITOR") (pin "2") (pinfunction "2_2") (pintype "passive"))
    )
    (net (code "25") (name "Net-(EPD_C1-Pad2)") (class "Default")
      (node (ref "EPD_C1") (pin "2") (pinfunction "2_2") (pintype "passive"))
      (node (ref "J1") (pin "4") (pinfunction "4_4") (pintype "bidirectional"))
    )
    (net (code "26") (name "Net-(EPD_C2-Pad2)") (class "Default")
      (node (ref "EPD_C2") (pin "2") (pinfunction "2_2") (pintype "passive"))
      (node (ref "J1") (pin "5") (pinfunction "5_5") (pintype "bidirectional"))
    )
    (net (code "27") (name "Net-(EPD_C6-Pad2)") (class "Default")
      (node (ref "EPD_C6") (pin "2") (pinfunction "2_2") (pintype "passive"))
      (node (ref "J1") (pin "18") (pinfunction "18_18") (pintype "bidirectional"))
    )
    (net (code "28") (name "Net-(EPD_C7-Pad2)") (class "Default")
      (node (ref "EPD_C7") (pin "2") (pinfunction "2_2") (pintype "passive"))
      (node (ref "J1") (pin "19") (pinfunction "19_19") (pintype "bidirectional"))
    )
    (net (code "29") (name "Net-(EPD_C8-Pad2)") (class "Default")
      (node (ref "EPD_C8") (pin "2") (pinfunction "2_2") (pintype "passive"))
      (node (ref "J1") (pin "20") (pinfunction "20_20") (pintype "bidirectional"))
    )
    (net (code "30") (name "Net-(EPD_C10-Pad2)") (class "Default")
      (node (ref "EPD_C10") (pin "2") (pinfunction "2_2") (pintype "passive"))
      (node (ref "J1") (pin "22") (pinfunction "22_22") (pintype "bidirectional"))
    )
    (net (code "31") (name "Net-(EPD_C12-Pad2)") (class "Default")
      (node (ref "EPD_C12") (pin "2") (pinfunction "2_2") (pintype "passive"))
      (node (ref "J1") (pin "24") (pinfunction "24_24") (pintype "bidirectional"))
    )
    (net (code "32") (name "Net-(IC1-CT)") (class "Default")
      (node (ref "C_DELAY") (pin "1") (pinfunction "1_1") (pintype "passive"))
      (node (ref "IC1") (pin "5") (pinfunction "CT_5") (pintype "bidirectional"))
    )
    (net (code "33") (name "Net-(J2-PadA5)") (class "Default")
      (node (ref "J2") (pin "A5") (pinfunction "A5_A5") (pintype "bidirectional"))
      (node (ref "R2-USB1") (pin "2") (pinfunction "2_2") (pintype "passive"))
    )
    (net (code "34") (name "Net-(J2-PadB5)") (class "Default")
      (node (ref "J2") (pin "B5") (pinfunction "B5_B5") (pintype "bidirectional"))
      (node (ref "R2-USB") (pin "1") (pinfunction "1_1") (pintype "passive"))
    )
    (net (code "35") (name "Net-(MCP73831-PROG)") (class "Default")
      (node (ref "MCP73831") (pin "5") (pinfunction "PROG_5") (pintype "input"))
      (node (ref "R2_BAT") (pin "2") (pinfunction "2_2") (pintype "passive"))
    )
    (net (code "36") (name "Net-(MCP73831-STAT)") (class "Default")
      (node (ref "MCP73831") (pin "1") (pinfunction "STAT_1") (pintype "output"))
      (node (ref "R1_BAT") (pin "2") (pinfunction "2_2") (pintype "passive"))
    )
    (net (code "37") (name "PREVGH") (class "Default")
      (node (ref "D5") (pin "1") (pinfunction "K_1") (pintype "bidirectional"))
      (node (ref "EPD_C9") (pin "2") (pinfunction "2_2") (pintype "passive"))
      (node (ref "J1") (pin "21") (pinfunction "21_21") (pintype "bidirectional"))
    )
    (net (code "38") (name "PREVGL") (class "Default")
      (node (ref "D4") (pin "2") (pinfunction "A_2") (pintype "bidirectional"))
      (node (ref "EPD_C11") (pin "2") (pinfunction "2_2") (pintype "passive"))
      (node (ref "J1") (pin "23") (pinfunction "23_23") (pintype "bidirectional"))
    )
    (net (code "39") (name "RESE") (class "Default")
      (node (ref "J1") (pin "3") (pinfunction "3_3") (pintype "bidirectional"))
      (node (ref "Q3") (pin "2") (pinfunction "S_2") (pintype "bidirectional"))
      (node (ref "R3") (pin "2") (pinfunction "2_2") (pintype "passive"))
    )
    (net (code "40") (name "RESE'") (class "Default")
      (node (ref "R2") (pin "2") (pinfunction "2_2") (pintype "passive"))
      (node (ref "R3") (pin "1") (pinfunction "1_1") (pintype "passive"))
      (node (ref "SJ1") (pin "2") (pinfunction "2_2") (pintype "passive"))
    )
    (net (code "41") (name "RESET") (class "Default")
      (node (ref "C5") (pin "1") (pinfunction "1_1") (pintype "passive"))
      (node (ref "IC1") (pin "1") (pinfunction "VOUT_1") (pintype "bidirectional"))
      (node (ref "RESET_BUTTON") (pin "3") (pinfunction "3_3") (pintype "passive"))
      (node (ref "RESET_BUTTON") (pin "4") (pinfunction "4_4") (pintype "passive"))
      (node (ref "R_RESET") (pin "1") (pinfunction "1_1") (pintype "passive"))
      (node (ref "U2") (pin "3") (pinfunction "EN_3") (pintype "input"))
    )
    (net (code "42") (name "RTC_RST") (class "Default")
      (node (ref "U2") (pin "16") (pinfunction "IO18_16") (pintype "bidirectional"))
      (node (ref "U3") (pin "4") (pinfunction "~{RST}_4") (pintype "input"))
    )
    (net (code "43") (name "RX") (class "Default")
      (node (ref "TP2") (pin "TP") (pinfunction "TP_TP") (pintype "input"))
      (node (ref "U2") (pin "24") (pinfunction "RXD0/GPIO17_24") (pintype "bidirectional"))
    )
    (net (code "44") (name "SCK") (class "Default")
      (node (ref "D10") (pin "2") (pinfunction "2_2") (pintype "passive"))
      (node (ref "J1") (pin "13") (pinfunction "13_13") (pintype "bidirectional"))
      (node (ref "J4") (pin "P5") (pinfunction "CLK_P5") (pintype "bidirectional"))
      (node (ref "R6") (pin "1") (pinfunction "1_1") (pintype "passive"))
      (node (ref "TP8") (pin "TP") (pinfunction "TP_TP") (pintype "input"))
      (node (ref "U1") (pin "6") (pinfunction "CLK_6") (pintype "input"))
      (node (ref "U2") (pin "6") (pinfunction "IO6_6") (pintype "bidirectional"))
    )
    (net (code "45") (name "SCL") (class "Default")
      (node (ref "J3") (pin "4") (pinfunction "4_4") (pintype "passive"))
      (node (ref "R2-PINH") (pin "1") (pinfunction "1_1") (pintype "passive"))
      (node (ref "SENSOR2") (pin "4") (pinfunction "SCK_4") (pintype "input"))
      (node (ref "U2") (pin "20") (pinfunction "IO22_20") (pintype "bidirectional"))
      (node (ref "U3") (pin "16") (pinfunction "SCL_16") (pintype "input"))
      (node (ref "U4") (pin "7") (pinfunction "SCL_7") (pintype "input"))
    )
    (net (code "46") (name "SDA") (class "Default")
      (node (ref "J3") (pin "3") (pinfunction "3_3") (pintype "passive"))
      (node (ref "R1_PINH") (pin "1") (pinfunction "1_1") (pintype "passive"))
      (node (ref "SENSOR2") (pin "3") (pinfunction "SDI_3") (pintype "bidirectional"))
      (node (ref "U2") (pin "19") (pinfunction "IO21_19") (pintype "bidirectional"))
      (node (ref "U3") (pin "15") (pinfunction "SDA_15") (pintype "bidirectional"))
      (node (ref "U4") (pin "8") (pinfunction "SDA_8") (pintype "bidirectional"))
    )
    (net (code "47") (name "SRC") (class "Default")
      (node (ref "C4") (pin "2") (pinfunction "2_2") (pintype "passive"))
      (node (ref "D5") (pin "2") (pinfunction "A_2") (pintype "bidirectional"))
      (node (ref "L1") (pin "1") (pinfunction "1_1") (pintype "passive"))
      (node (ref "Q3") (pin "3") (pinfunction "D_3") (pintype "bidirectional"))
    )
    (net (code "48") (name "SS_SD") (class "Default")
      (node (ref "D8") (pin "2") (pinfunction "2_2") (pintype "passive"))
      (node (ref "J4") (pin "P2") (pinfunction "CD/DAT3_P2") (pintype "bidirectional"))
      (node (ref "R10") (pin "1") (pinfunction "1_1") (pintype "passive"))
      (node (ref "U2") (pin "4") (pinfunction "IO4_4") (pintype "bidirectional"))
    )
    (net (code "49") (name "TX") (class "Default")
      (node (ref "TP1") (pin "TP") (pinfunction "TP_TP") (pintype "input"))
      (node (ref "U2") (pin "25") (pinfunction "TXD0/GPIO16_25") (pintype "bidirectional"))
    )
    (net (code "50") (name "USB_D+_N") (class "Default")
      (node (ref "D1") (pin "6") (pinfunction "I/O1_2_6") (pintype "bidirectional"))
      (node (ref "U2") (pin "13") (pinfunction "IO12_13") (pintype "bidirectional"))
    )
    (net (code "51") (name "USB_D+_P") (class "Default")
      (node (ref "D1") (pin "4") (pinfunction "I/O2_2_4") (pintype "bidirectional"))
      (node (ref "U2") (pin "14") (pinfunction "IO13_14") (pintype "bidirectional"))
    )
    (net (code "52") (name "VBAT") (class "Default")
      (node (ref "C2_BAT") (pin "1") (pinfunction "1_1") (pintype "passive"))
      (node (ref "MCP73831") (pin "3") (pinfunction "VBAT_3") (pintype "power_in"))
      (node (ref "Q1") (pin "3") (pinfunction "D_3") (pintype "bidirectional"))
      (node (ref "TP3") (pin "TP") (pinfunction "TP_TP") (pintype "input"))
      (node (ref "U4") (pin "2") (pinfunction "CELL_2") (pintype "power_in"))
      (node (ref "U4") (pin "3") (pinfunction "VDD_3") (pintype "power_in"))
    )
    (net (code "53") (name "VBUS") (class "Default")
      (node (ref "C1_BAT") (pin "1") (pinfunction "1_1") (pintype "passive"))
      (node (ref "C4_USB") (pin "1") (pinfunction "1_1") (pintype "passive"))
      (node (ref "C5_USB") (pin "1") (pinfunction "1_1") (pintype "passive"))
      (node (ref "CHG_LED") (pin "A") (pinfunction "A_A") (pintype "passive"))
      (node (ref "D1") (pin "2") (pinfunction "GND_2") (pintype "bidirectional"))
      (node (ref "D2") (pin "2") (pinfunction "ANODE_2") (pintype "bidirectional"))
      (node (ref "MCP73831") (pin "4") (pinfunction "VIN_4") (pintype "power_in"))
      (node (ref "PFMF.050.1") (pin "2") (pinfunction "2_2") (pintype "passive"))
      (node (ref "Q1") (pin "1") (pinfunction "G_1") (pintype "bidirectional"))
      (node (ref "R1_PWRUSB") (pin "2") (pinfunction "2_2") (pintype "passive"))
      (node (ref "TP14") (pin "TP") (pinfunction "TP_TP") (pintype "input"))
    )
    (net (code "54") (name "VRTC") (class "Default")
      (node (ref "C10_SUPERCAP") (pin "2") (pinfunction "2_2") (pintype "passive"))
      (node (ref "C8") (pin "1") (pinfunction "1_1") (pintype "passive"))
      (node (ref "R_CAPACITOR") (pin "1") (pinfunction "1_1") (pintype "passive"))
      (node (ref "U3") (pin "14") (pinfunction "VBAT_14") (pintype "power_in"))
    )
    (net (code "55") (name "VUSB") (class "Default")
      (node (ref "J2") (pin "A4") (pinfunction "A4_A4") (pintype "bidirectional"))
      (node (ref "J2") (pin "A9") (pinfunction "A9_A9") (pintype "bidirectional"))
      (node (ref "J2") (pin "B4") (pinfunction "B4_B4") (pintype "bidirectional"))
      (node (ref "J2") (pin "B9") (pinfunction "B9_B9") (pintype "bidirectional"))
      (node (ref "PFMF.050.1") (pin "1") (pinfunction "1_1") (pintype "passive"))
    )
    (net (code "56") (name "unconnected-(IC1-NC-Pad4)") (class "Default")
      (node (ref "IC1") (pin "4") (pinfunction "NC_4") (pintype "no_connect"))
    )
    (net (code "57") (name "unconnected-(IC4-NC-Pad4)") (class "Default")
      (node (ref "IC4") (pin "4") (pinfunction "NC_4") (pintype "no_connect"))
    )
    (net (code "58") (name "unconnected-(J1-Pad1)") (class "Default")
      (node (ref "J1") (pin "1") (pinfunction "1_1") (pintype "bidirectional"))
    )
    (net (code "59") (name "unconnected-(J1-Pad6)") (class "Default")
      (node (ref "J1") (pin "6") (pinfunction "6_6") (pintype "bidirectional"))
    )
    (net (code "60") (name "unconnected-(J1-Pad7)") (class "Default")
      (node (ref "J1") (pin "7") (pinfunction "7_7") (pintype "bidirectional"))
    )
    (net (code "61") (name "unconnected-(J2-PadA8)") (class "Default")
      (node (ref "J2") (pin "A8") (pinfunction "A8_A8") (pintype "bidirectional"))
    )
    (net (code "62") (name "unconnected-(J2-PadB8)") (class "Default")
      (node (ref "J2") (pin "B8") (pinfunction "B8_B8") (pintype "bidirectional"))
    )
    (net (code "63") (name "unconnected-(J4-DAT1-PadP8)") (class "Default")
      (node (ref "J4") (pin "P8") (pinfunction "DAT1_P8") (pintype "bidirectional"))
    )
    (net (code "64") (name "unconnected-(J4-DAT2-PadP1)") (class "Default")
      (node (ref "J4") (pin "P1") (pinfunction "DAT2_P1") (pintype "bidirectional"))
    )
    (net (code "65") (name "unconnected-(J4-DETECTION_1-PadS1)") (class "Default")
      (node (ref "J4") (pin "S1") (pinfunction "DETECTION_1_S1") (pintype "bidirectional"))
    )
    (net (code "66") (name "unconnected-(J4-DETECTION_2-PadS2)") (class "Default")
      (node (ref "J4") (pin "S2") (pinfunction "DETECTION_2_S2") (pintype "bidirectional"))
    )
    (net (code "67") (name "unconnected-(U2-NC-Pad22)") (class "Default")
      (node (ref "U2") (pin "22") (pinfunction "NC_22") (pintype "no_connect"))
    )
    (net (code "68") (name "unconnected-(U4-~{ALERT}-Pad5)") (class "Default")
      (node (ref "U4") (pin "5") (pinfunction "~{ALERT}_5") (pintype "output"))
    )
  )
)
